# PCB-PWR-CON3.net
KiCad netlist of a schematic drawn in EAGLE
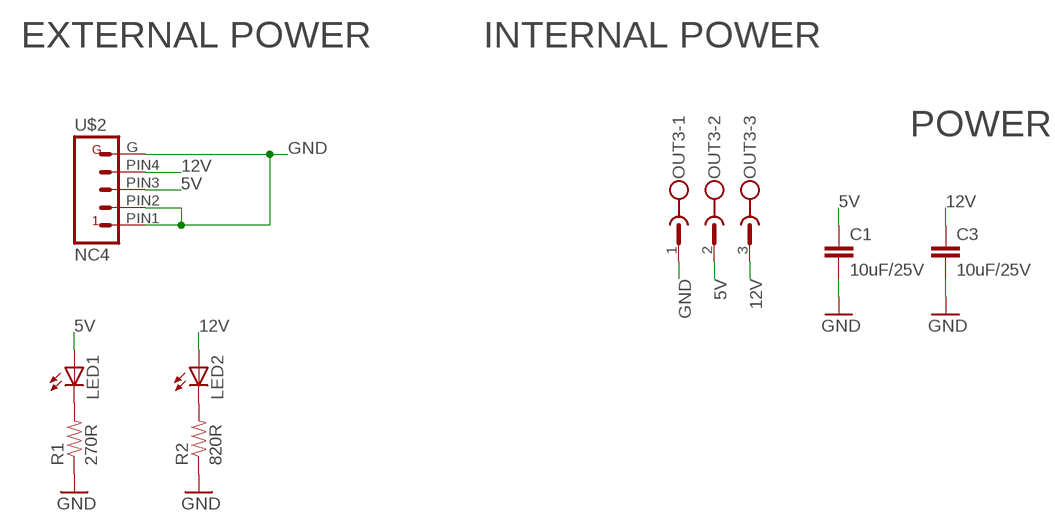
[diagram p0: schematic, sheet 1]

(export (version "E")
  (design (tool "Eeschema 10.0.6"))
  (components
    (comp (ref "C1")
      (value "10uF/25V")
      (footprint "eagle-import:0805")
      (libsource (lib "eagle-import") (part "CAP0805"))
    )
    (comp (ref "C3")
      (value "10uF/25V")
      (footprint "eagle-import:0805")
      (libsource (lib "eagle-import") (part "CAP0805"))
    )
    (comp (ref "LED1")
      (value "LED3MM")
      (footprint "eagle-import:LED3MM")
      (libsource (lib "eagle-import") (part "LED3MM"))
    )
    (comp (ref "LED2")
      (value "LED3MM")
      (footprint "eagle-import:LED3MM")
      (libsource (lib "eagle-import") (part "LED3MM"))
    )
    (comp (ref "OUT3")
      (value "CON1")
      (footprint "eagle-import:MSTBV3")
      (fields (field (name "MPN") "MSTBV 2,5/3-GF-5.08"))
      (libsource (lib "eagle-import") (part "MSTBV3"))
    )
    (comp (ref "R1")
      (value "270R")
      (footprint "eagle-import:0603-RES")
      (libsource (lib "eagle-import") (part "RESISTOR0603-RES"))
    )
    (comp (ref "R2")
      (value "820R")
      (footprint "eagle-import:0603-RES")
      (libsource (lib "eagle-import") (part "RESISTOR0603-RES"))
    )
    (comp (ref "U$2")
      (value "NC4")
      (footprint "eagle-import:NC4-MD-L1")
      (libsource (lib "eagle-import") (part "NC4"))
    )
  )
  (nets
    (net (code "1") (name "/5V") (class "Default")
      (node (ref "C1") (pin "1") (pinfunction "1_1") (pintype "passive"))
      (node (ref "LED1") (pin "A") (pinfunction "A_A") (pintype "passive"))
      (node (ref "OUT3") (pin "2") (pinfunction "1_2") (pintype "passive"))
      (node (ref "U$2") (pin "PIN3") (pinfunction "3_PIN3") (pintype "passive"))
    )
    (net (code "2") (name "/12V") (class "Default")
      (node (ref "C3") (pin "1") (pinfunction "1_1") (pintype "passive"))
      (node (ref "LED2") (pin "A") (pinfunction "A_A") (pintype "passive"))
      (node (ref "OUT3") (pin "3") (pinfunction "1_3") (pintype "passive"))
      (node (ref "U$2") (pin "PIN4") (pinfunction "4_PIN4") (pintype "passive"))
    )
    (net (code "3") (name "GND") (class "Default")
      (node (ref "C1") (pin "2") (pinfunction "2_2") (pintype "passive"))
      (node (ref "C3") (pin "2") (pinfunction "2_2") (pintype "passive"))
      (node (ref "OUT3") (pin "1") (pinfunction "1_1") (pintype "passive"))
      (node (ref "R1") (pin "1") (pinfunction "1_1") (pintype "passive"))
      (node (ref "R2") (pin "1") (pinfunction "1_1") (pintype "passive"))
      (node (ref "U$2") (pin "G") (pinfunction "G_G") (pintype "passive"))
      (node (ref "U$2") (pin "PIN1") (pinfunction "1_PIN1") (pintype "passive"))
      (node (ref "U$2") (pin "PIN2") (pinfunction "2_PIN2") (pintype "passive"))
    )
    (net (code "4") (name "Net-(LED1-C)") (class "Default")
      (node (ref "LED1") (pin "K") (pinfunction "C_K") (pintype "passive"))
      (node (ref "R1") (pin "2") (pinfunction "2_2") (pintype "passive"))
    )
    (net (code "5") (name "Net-(LED2-C)") (class "Default")
      (node (ref "LED2") (pin "K") (pinfunction "C_K") (pintype "passive"))
      (node (ref "R2") (pin "2") (pinfunction "2_2") (pintype "passive"))
    )
  )
)
